# DDR2Module.net
KiCad netlist of a schematic drawn in Altium Designer
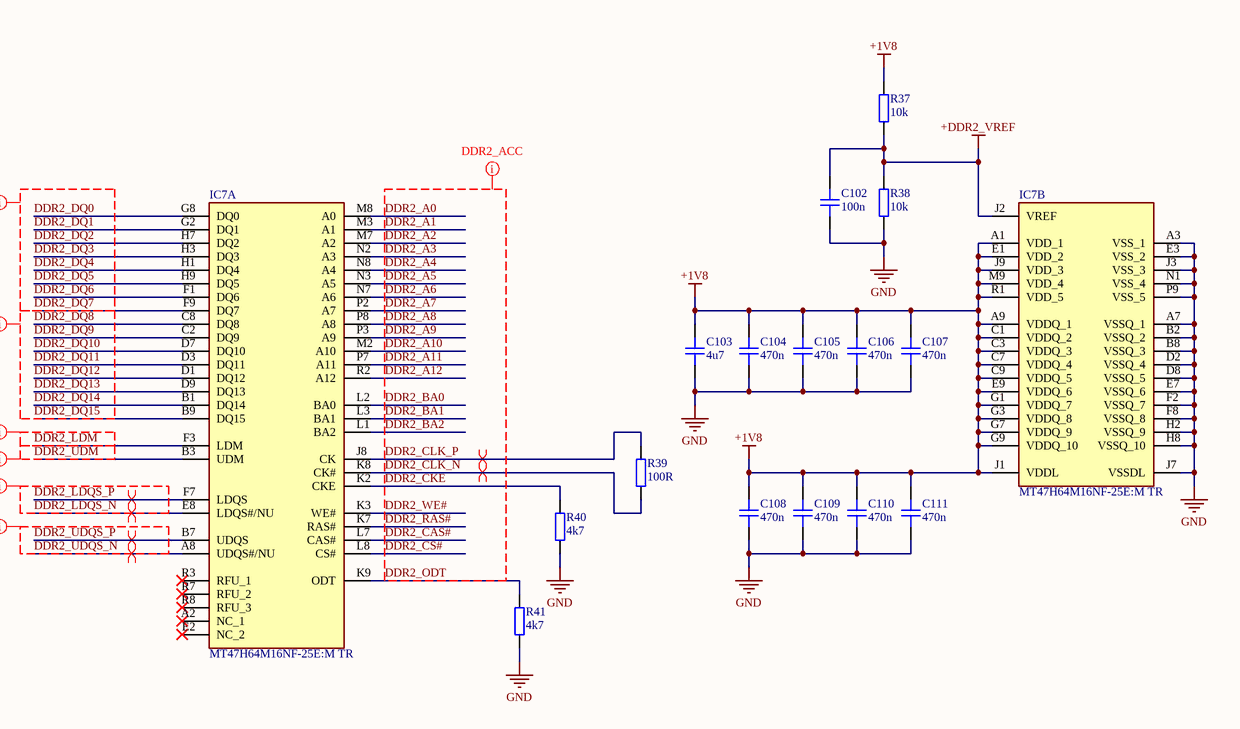
[diagram p0: DDR2Module.SchDoc]

(export (version "E")
  (design (tool "Eeschema 10.0.6"))
  (components
    (comp (ref "C102")
      (value "100n")
      (footprint "CAP_0402")
      (description "Capacitor SMD 0402")
      (libsource (lib "Schematic-Lib-PhilsLab") (part "CAP_0402"))
    )
    (comp (ref "C103")
      (value "4u7")
      (footprint "CAP_0402")
      (description "Capacitor SMD 0402")
      (libsource (lib "Schematic-Lib-PhilsLab") (part "CAP_0402"))
    )
    (comp (ref "C104")
      (value "470n")
      (footprint "CAP_0201")
      (description "Capacitor SMD 0201")
      (libsource (lib "Schematic-Lib-PhilsLab") (part "CAP_0201"))
    )
    (comp (ref "C105")
      (value "470n")
      (footprint "CAP_0201")
      (description "Capacitor SMD 0201")
      (libsource (lib "Schematic-Lib-PhilsLab") (part "CAP_0201"))
    )
    (comp (ref "C106")
      (value "470n")
      (footprint "CAP_0201")
      (description "Capacitor SMD 0201")
      (libsource (lib "Schematic-Lib-PhilsLab") (part "CAP_0201"))
    )
    (comp (ref "C107")
      (value "470n")
      (footprint "CAP_0201")
      (description "Capacitor SMD 0201")
      (libsource (lib "Schematic-Lib-PhilsLab") (part "CAP_0201"))
    )
    (comp (ref "C108")
      (value "470n")
      (footprint "CAP_0201")
      (description "Capacitor SMD 0201")
      (libsource (lib "Schematic-Lib-PhilsLab") (part "CAP_0201"))
    )
    (comp (ref "C109")
      (value "470n")
      (footprint "CAP_0201")
      (description "Capacitor SMD 0201")
      (libsource (lib "Schematic-Lib-PhilsLab") (part "CAP_0201"))
    )
    (comp (ref "C110")
      (value "470n")
      (footprint "CAP_0201")
      (description "Capacitor SMD 0201")
      (libsource (lib "Schematic-Lib-PhilsLab") (part "CAP_0201"))
    )
    (comp (ref "C111")
      (value "470n")
      (footprint "CAP_0201")
      (description "Capacitor SMD 0201")
      (libsource (lib "Schematic-Lib-PhilsLab") (part "CAP_0201"))
    )
    (comp (ref "IC7")
      (value "MT47H64M16NF-25E:M TR")
      (footprint "Footprint-Lib-PhilsLab:BGA84C80P9X15_800X1250X120")
      (description "Integrated Circuit")
      (fields (field (name "MOUSER PART NUMBER") "340-248361-REEL"))
      (libsource (lib "Schematic-Lib-PhilsLab") (part "MT47H64M16NF-25E{colon}M TR"))
    )
    (comp (ref "R37")
      (value "10k")
      (footprint "RES_0402")
      (description "Resistor SMD 0402")
      (libsource (lib "Schematic-Lib-PhilsLab") (part "RES_0402"))
    )
    (comp (ref "R38")
      (value "10k")
      (footprint "RES_0402")
      (description "Resistor SMD 0402")
      (libsource (lib "Schematic-Lib-PhilsLab") (part "RES_0402"))
    )
    (comp (ref "R39")
      (value "100R")
      (footprint "RES_0201")
      (description "Resistor SMD 0201")
      (libsource (lib "Schematic-Lib-PhilsLab") (part "RES_0201"))
    )
    (comp (ref "R40")
      (value "4k7")
      (footprint "RES_0201")
      (description "Resistor SMD 0201")
      (libsource (lib "Schematic-Lib-PhilsLab") (part "RES_0201"))
    )
    (comp (ref "R41")
      (value "4k7")
      (footprint "RES_0201")
      (description "Resistor SMD 0201")
      (libsource (lib "Schematic-Lib-PhilsLab") (part "RES_0201"))
    )
  )
  (nets
    (net (code "1") (name "+1V8") (class "Default")
      (node (ref "C103") (pin "2") (pinfunction "2_2") (pintype "passive"))
      (node (ref "C104") (pin "2") (pinfunction "2_2") (pintype "passive"))
      (node (ref "C105") (pin "2") (pinfunction "2_2") (pintype "passive"))
      (node (ref "C106") (pin "2") (pinfunction "2_2") (pintype "passive"))
      (node (ref "C107") (pin "2") (pinfunction "2_2") (pintype "passive"))
      (node (ref "C108") (pin "2") (pinfunction "2_2") (pintype "passive"))
      (node (ref "C109") (pin "2") (pinfunction "2_2") (pintype "passive"))
      (node (ref "C110") (pin "2") (pinfunction "2_2") (pintype "passive"))
      (node (ref "C111") (pin "2") (pinfunction "2_2") (pintype "passive"))
      (node (ref "IC7") (pin "A1") (pinfunction "VDD_1_A1") (pintype "passive"))
      (node (ref "IC7") (pin "A9") (pinfunction "VDDQ_1_A9") (pintype "passive"))
      (node (ref "IC7") (pin "C1") (pinfunction "VDDQ_2_C1") (pintype "passive"))
      (node (ref "IC7") (pin "C3") (pinfunction "VDDQ_3_C3") (pintype "passive"))
      (node (ref "IC7") (pin "C7") (pinfunction "VDDQ_4_C7") (pintype "passive"))
      (node (ref "IC7") (pin "C9") (pinfunction "VDDQ_5_C9") (pintype "passive"))
      (node (ref "IC7") (pin "E1") (pinfunction "VDD_2_E1") (pintype "passive"))
      (node (ref "IC7") (pin "E9") (pinfunction "VDDQ_6_E9") (pintype "passive"))
      (node (ref "IC7") (pin "G1") (pinfunction "VDDQ_7_G1") (pintype "passive"))
      (node (ref "IC7") (pin "G3") (pinfunction "VDDQ_8_G3") (pintype "passive"))
      (node (ref "IC7") (pin "G7") (pinfunction "VDDQ_9_G7") (pintype "passive"))
      (node (ref "IC7") (pin "G9") (pinfunction "VDDQ_10_G9") (pintype "passive"))
      (node (ref "IC7") (pin "J1") (pinfunction "VDDL_J1") (pintype "passive"))
      (node (ref "IC7") (pin "J9") (pinfunction "VDD_3_J9") (pintype "passive"))
      (node (ref "IC7") (pin "M9") (pinfunction "VDD_4_M9") (pintype "passive"))
      (node (ref "IC7") (pin "R1") (pinfunction "VDD_5_R1") (pintype "passive"))
      (node (ref "R37") (pin "2") (pinfunction "2_2") (pintype "passive"))
    )
    (net (code "2") (name "+DDR2_VREF") (class "Default")
      (node (ref "C102") (pin "1") (pinfunction "1_1") (pintype "passive"))
      (node (ref "IC7") (pin "J2") (pinfunction "VREF_J2") (pintype "passive"))
      (node (ref "R37") (pin "1") (pinfunction "1_1") (pintype "passive"))
      (node (ref "R38") (pin "2") (pinfunction "2_2") (pintype "passive"))
    )
    (net (code "3") (name "/DDR2_A0") (class "Default")
      (node (ref "IC7") (pin "M8") (pinfunction "A0_M8") (pintype "passive"))
    )
    (net (code "4") (name "/DDR2_A1") (class "Default")
      (node (ref "IC7") (pin "M3") (pinfunction "A1_M3") (pintype "passive"))
    )
    (net (code "5") (name "/DDR2_A2") (class "Default")
      (node (ref "IC7") (pin "M7") (pinfunction "A2_M7") (pintype "passive"))
    )
    (net (code "6") (name "/DDR2_A3") (class "Default")
      (node (ref "IC7") (pin "N2") (pinfunction "A3_N2") (pintype "passive"))
    )
    (net (code "7") (name "/DDR2_A4") (class "Default")
      (node (ref "IC7") (pin "N8") (pinfunction "A4_N8") (pintype "passive"))
    )
    (net (code "8") (name "/DDR2_A5") (class "Default")
      (node (ref "IC7") (pin "N3") (pinfunction "A5_N3") (pintype "passive"))
    )
    (net (code "9") (name "/DDR2_A6") (class "Default")
      (node (ref "IC7") (pin "N7") (pinfunction "A6_N7") (pintype "passive"))
    )
    (net (code "10") (name "/DDR2_A7") (class "Default")
      (node (ref "IC7") (pin "P2") (pinfunction "A7_P2") (pintype "passive"))
    )
    (net (code "11") (name "/DDR2_A8") (class "Default")
      (node (ref "IC7") (pin "P8") (pinfunction "A8_P8") (pintype "passive"))
    )
    (net (code "12") (name "/DDR2_A9") (class "Default")
      (node (ref "IC7") (pin "P3") (pinfunction "A9_P3") (pintype "passive"))
    )
    (net (code "13") (name "/DDR2_A10") (class "Default")
      (node (ref "IC7") (pin "M2") (pinfunction "A10_M2") (pintype "passive"))
    )
    (net (code "14") (name "/DDR2_A11") (class "Default")
      (node (ref "IC7") (pin "P7") (pinfunction "A11_P7") (pintype "passive"))
    )
    (net (code "15") (name "/DDR2_A12") (class "Default")
      (node (ref "IC7") (pin "R2") (pinfunction "A12_R2") (pintype "passive"))
    )
    (net (code "16") (name "/DDR2_BA0") (class "Default")
      (node (ref "IC7") (pin "L2") (pinfunction "BA0_L2") (pintype "passive"))
    )
    (net (code "17") (name "/DDR2_BA1") (class "Default")
      (node (ref "IC7") (pin "L3") (pinfunction "BA1_L3") (pintype "passive"))
    )
    (net (code "18") (name "/DDR2_BA2") (class "Default")
      (node (ref "IC7") (pin "L1") (pinfunction "BA2_L1") (pintype "passive"))
    )
    (net (code "19") (name "/DDR2_CAS#") (class "Default")
      (node (ref "IC7") (pin "L7") (pinfunction "CAS#_L7") (pintype "passive"))
    )
    (net (code "20") (name "/DDR2_CKE") (class "Default")
      (node (ref "IC7") (pin "K2") (pinfunction "CKE_K2") (pintype "passive"))
      (node (ref "R40") (pin "2") (pinfunction "2_2") (pintype "passive"))
    )
    (net (code "21") (name "/DDR2_CLK_N") (class "Default")
      (node (ref "IC7") (pin "K8") (pinfunction "CK#_K8") (pintype "passive"))
      (node (ref "R39") (pin "1") (pinfunction "1_1") (pintype "passive"))
    )
    (net (code "22") (name "/DDR2_CLK_P") (class "Default")
      (node (ref "IC7") (pin "J8") (pinfunction "CK_J8") (pintype "passive"))
      (node (ref "R39") (pin "2") (pinfunction "2_2") (pintype "passive"))
    )
    (net (code "23") (name "/DDR2_CS#") (class "Default")
      (node (ref "IC7") (pin "L8") (pinfunction "CS#_L8") (pintype "passive"))
    )
    (net (code "24") (name "/DDR2_DQ0") (class "Default")
      (node (ref "IC7") (pin "G8") (pinfunction "DQ0_G8") (pintype "passive"))
    )
    (net (code "25") (name "/DDR2_DQ1") (class "Default")
      (node (ref "IC7") (pin "G2") (pinfunction "DQ1_G2") (pintype "passive"))
    )
    (net (code "26") (name "/DDR2_DQ2") (class "Default")
      (node (ref "IC7") (pin "H7") (pinfunction "DQ2_H7") (pintype "passive"))
    )
    (net (code "27") (name "/DDR2_DQ3") (class "Default")
      (node (ref "IC7") (pin "H3") (pinfunction "DQ3_H3") (pintype "passive"))
    )
    (net (code "28") (name "/DDR2_DQ4") (class "Default")
      (node (ref "IC7") (pin "H1") (pinfunction "DQ4_H1") (pintype "passive"))
    )
    (net (code "29") (name "/DDR2_DQ5") (class "Default")
      (node (ref "IC7") (pin "H9") (pinfunction "DQ5_H9") (pintype "passive"))
    )
    (net (code "30") (name "/DDR2_DQ6") (class "Default")
      (node (ref "IC7") (pin "F1") (pinfunction "DQ6_F1") (pintype "passive"))
    )
    (net (code "31") (name "/DDR2_DQ7") (class "Default")
      (node (ref "IC7") (pin "F9") (pinfunction "DQ7_F9") (pintype "passive"))
    )
    (net (code "32") (name "/DDR2_DQ8") (class "Default")
      (node (ref "IC7") (pin "C8") (pinfunction "DQ8_C8") (pintype "passive"))
    )
    (net (code "33") (name "/DDR2_DQ9") (class "Default")
      (node (ref "IC7") (pin "C2") (pinfunction "DQ9_C2") (pintype "passive"))
    )
    (net (code "34") (name "/DDR2_DQ10") (class "Default")
      (node (ref "IC7") (pin "D7") (pinfunction "DQ10_D7") (pintype "passive"))
    )
    (net (code "35") (name "/DDR2_DQ11") (class "Default")
      (node (ref "IC7") (pin "D3") (pinfunction "DQ11_D3") (pintype "passive"))
    )
    (net (code "36") (name "/DDR2_DQ12") (class "Default")
      (node (ref "IC7") (pin "D1") (pinfunction "DQ12_D1") (pintype "passive"))
    )
    (net (code "37") (name "/DDR2_DQ13") (class "Default")
      (node (ref "IC7") (pin "D9") (pinfunction "DQ13_D9") (pintype "passive"))
    )
    (net (code "38") (name "/DDR2_DQ14") (class "Default")
      (node (ref "IC7") (pin "B1") (pinfunction "DQ14_B1") (pintype "passive"))
    )
    (net (code "39") (name "/DDR2_DQ15") (class "Default")
      (node (ref "IC7") (pin "B9") (pinfunction "DQ15_B9") (pintype "passive"))
    )
    (net (code "40") (name "/DDR2_LDM") (class "Default")
      (node (ref "IC7") (pin "F3") (pinfunction "LDM_F3") (pintype "passive"))
    )
    (net (code "41") (name "/DDR2_LDQS_N") (class "Default")
      (node (ref "IC7") (pin "E8") (pinfunction "LDQS#/NU_E8") (pintype "passive"))
    )
    (net (code "42") (name "/DDR2_LDQS_P") (class "Default")
      (node (ref "IC7") (pin "F7") (pinfunction "LDQS_F7") (pintype "passive"))
    )
    (net (code "43") (name "/DDR2_ODT") (class "Default")
      (node (ref "IC7") (pin "K9") (pinfunction "ODT_K9") (pintype "passive"))
      (node (ref "R41") (pin "2") (pinfunction "2_2") (pintype "passive"))
    )
    (net (code "44") (name "/DDR2_RAS#") (class "Default")
      (node (ref "IC7") (pin "K7") (pinfunction "RAS#_K7") (pintype "passive"))
    )
    (net (code "45") (name "/DDR2_UDM") (class "Default")
      (node (ref "IC7") (pin "B3") (pinfunction "UDM_B3") (pintype "passive"))
    )
    (net (code "46") (name "/DDR2_UDQS_N") (class "Default")
      (node (ref "IC7") (pin "A8") (pinfunction "UDQS#/NU_A8") (pintype "passive"))
    )
    (net (code "47") (name "/DDR2_UDQS_P") (class "Default")
      (node (ref "IC7") (pin "B7") (pinfunction "UDQS_B7") (pintype "passive"))
    )
    (net (code "48") (name "/DDR2_WE#") (class "Default")
      (node (ref "IC7") (pin "K3") (pinfunction "WE#_K3") (pintype "passive"))
    )
    (net (code "49") (name "GND") (class "Default")
      (node (ref "C102") (pin "2") (pinfunction "2_2") (pintype "passive"))
      (node (ref "C103") (pin "1") (pinfunction "1_1") (pintype "passive"))
      (node (ref "C104") (pin "1") (pinfunction "1_1") (pintype "passive"))
      (node (ref "C105") (pin "1") (pinfunction "1_1") (pintype "passive"))
      (node (ref "C106") (pin "1") (pinfunction "1_1") (pintype "passive"))
      (node (ref "C107") (pin "1") (pinfunction "1_1") (pintype "passive"))
      (node (ref "C108") (pin "1") (pinfunction "1_1") (pintype "passive"))
      (node (ref "C109") (pin "1") (pinfunction "1_1") (pintype "passive"))
      (node (ref "C110") (pin "1") (pinfunction "1_1") (pintype "passive"))
      (node (ref "C111") (pin "1") (pinfunction "1_1") (pintype "passive"))
      (node (ref "IC7") (pin "A3") (pinfunction "VSS_1_A3") (pintype "passive"))
      (node (ref "IC7") (pin "A7") (pinfunction "VSSQ_1_A7") (pintype "passive"))
      (node (ref "IC7") (pin "B2") (pinfunction "VSSQ_2_B2") (pintype "passive"))
      (node (ref "IC7") (pin "B8") (pinfunction "VSSQ_3_B8") (pintype "passive"))
      (node (ref "IC7") (pin "D2") (pinfunction "VSSQ_4_D2") (pintype "passive"))
      (node (ref "IC7") (pin "D8") (pinfunction "VSSQ_5_D8") (pintype "passive"))
      (node (ref "IC7") (pin "E3") (pinfunction "VSS_2_E3") (pintype "passive"))
      (node (ref "IC7") (pin "E7") (pinfunction "VSSQ_6_E7") (pintype "passive"))
      (node (ref "IC7") (pin "F2") (pinfunction "VSSQ_7_F2") (pintype "passive"))
      (node (ref "IC7") (pin "F8") (pinfunction "VSSQ_8_F8") (pintype "passive"))
      (node (ref "IC7") (pin "H2") (pinfunction "VSSQ_9_H2") (pintype "passive"))
      (node (ref "IC7") (pin "H8") (pinfunction "VSSQ_10_H8") (pintype "passive"))
      (node (ref "IC7") (pin "J3") (pinfunction "VSS_3_J3") (pintype "passive"))
      (node (ref "IC7") (pin "J7") (pinfunction "VSSDL_J7") (pintype "passive"))
      (node (ref "IC7") (pin "N1") (pinfunction "VSS_4_N1") (pintype "passive"))
      (node (ref "IC7") (pin "P9") (pinfunction "VSS_5_P9") (pintype "passive"))
      (node (ref "R38") (pin "1") (pinfunction "1_1") (pintype "passive"))
      (node (ref "R40") (pin "1") (pinfunction "1_1") (pintype "passive"))
      (node (ref "R41") (pin "1") (pinfunction "1_1") (pintype "passive"))
    )
    (net (code "50") (name "unconnected-(IC7A-NC_1-PadA2)") (class "Default")
      (node (ref "IC7") (pin "A2") (pinfunction "NC_1_A2") (pintype "passive+no_connect"))
    )
    (net (code "51") (name "unconnected-(IC7A-NC_2-PadE2)") (class "Default")
      (node (ref "IC7") (pin "E2") (pinfunction "NC_2_E2") (pintype "passive+no_connect"))
    )
    (net (code "52") (name "unconnected-(IC7A-RFU_1-PadR3)") (class "Default")
      (node (ref "IC7") (pin "R3") (pinfunction "RFU_1_R3") (pintype "passive+no_connect"))
    )
    (net (code "53") (name "unconnected-(IC7A-RFU_2-PadR7)") (class "Default")
      (node (ref "IC7") (pin "R7") (pinfunction "RFU_2_R7") (pintype "passive+no_connect"))
    )
    (net (code "54") (name "unconnected-(IC7A-RFU_3-PadR8)") (class "Default")
      (node (ref "IC7") (pin "R8") (pinfunction "RFU_3_R8") (pintype "passive+no_connect"))
    )
  )
)
